# Eyebot_powerdist.net
KiCad netlist of a schematic drawn in EAGLE
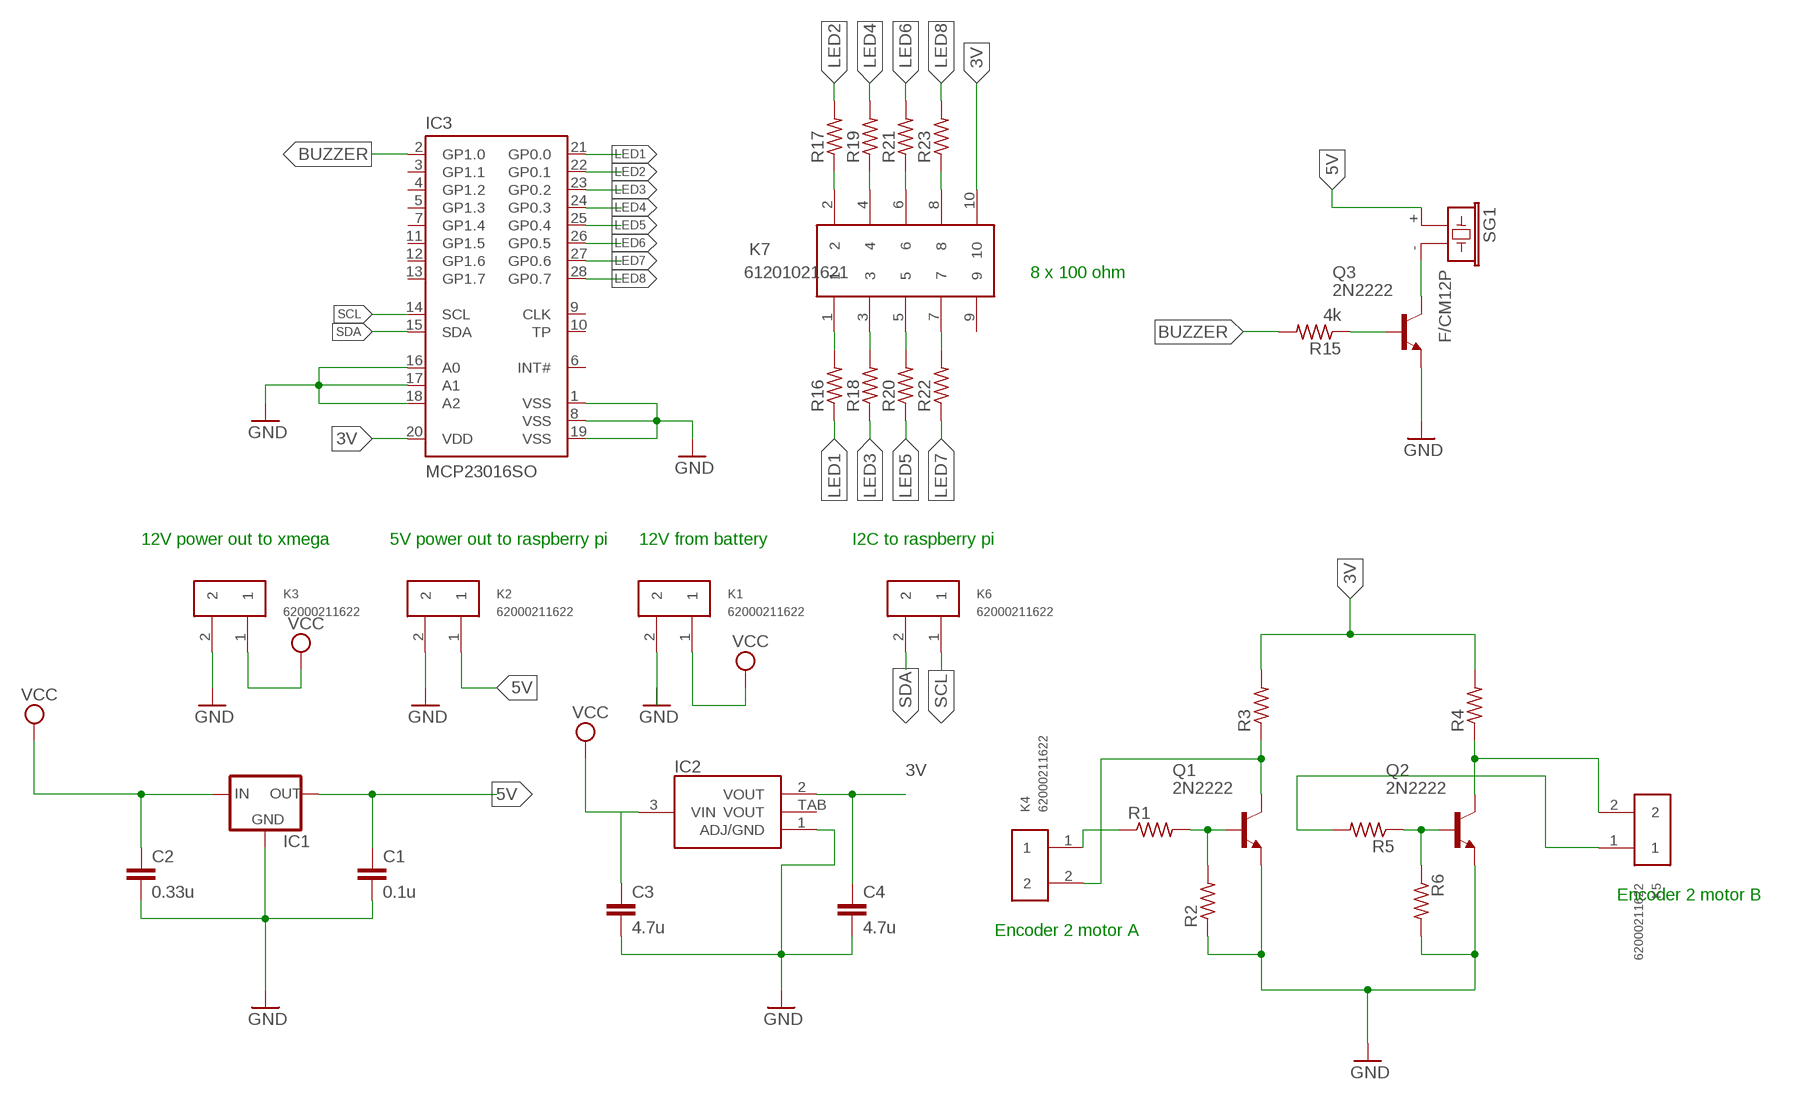
[diagram p0: schematic, sheet 1]

(export (version "E")
  (design (tool "Eeschema 10.0.6"))
  (components
    (comp (ref "C1")
      (value "0.1u")
      (footprint "eagle-import:AXIAL-5MM")
      (libsource (lib "eagle-import") (part "CAP_"))
    )
    (comp (ref "C2")
      (value "0.33u")
      (footprint "eagle-import:CAP-PTH-SMALL")
      (libsource (lib "eagle-import") (part "CAPPTH"))
    )
    (comp (ref "C3")
      (value "4.7u")
      (footprint "eagle-import:1206")
      (libsource (lib "eagle-import") (part "CAP1206"))
    )
    (comp (ref "C4")
      (value "4.7u")
      (footprint "eagle-import:1206")
      (libsource (lib "eagle-import") (part "CAP1206"))
    )
    (comp (ref "IC1")
      (value "V_REG_78XX-TO-220")
      (footprint "eagle-import:TO-220-ALT")
      (libsource (lib "eagle-import") (part "V_REG_78XX-TO-220"))
    )
    (comp (ref "IC2")
      (value "LDO1117-SOT223")
      (footprint "eagle-import:SOT223-3L")
      (libsource (lib "eagle-import") (part "LDO1117-SOT223"))
    )
    (comp (ref "IC3")
      (value "MCP23016SO")
      (footprint "eagle-import:SO-28W")
      (libsource (lib "eagle-import") (part "MCP23016SO"))
    )
    (comp (ref "K1")
      (value "62000211622")
      (footprint "eagle-import:62000211622")
      (libsource (lib "eagle-import") (part "62000211622"))
    )
    (comp (ref "K2")
      (value "62000211622")
      (footprint "eagle-import:62000211622")
      (libsource (lib "eagle-import") (part "62000211622"))
    )
    (comp (ref "K3")
      (value "62000211622")
      (footprint "eagle-import:62000211622")
      (libsource (lib "eagle-import") (part "62000211622"))
    )
    (comp (ref "K4")
      (value "62000211622")
      (footprint "eagle-import:62000211622")
      (libsource (lib "eagle-import") (part "62000211622"))
    )
    (comp (ref "K5")
      (value "62000211622")
      (footprint "eagle-import:62000211622")
      (libsource (lib "eagle-import") (part "62000211622"))
    )
    (comp (ref "K6")
      (value "62000211622")
      (footprint "eagle-import:62000211622")
      (libsource (lib "eagle-import") (part "62000211622"))
    )
    (comp (ref "K7")
      (value "61201021621")
      (footprint "eagle-import:61201021621")
      (libsource (lib "eagle-import") (part "61201021621"))
    )
    (comp (ref "Q1")
      (value "2N2222")
      (footprint "eagle-import:TO18")
      (libsource (lib "eagle-import") (part "2N2222"))
    )
    (comp (ref "Q2")
      (value "2N2222")
      (footprint "eagle-import:TO18")
      (libsource (lib "eagle-import") (part "2N2222"))
    )
    (comp (ref "Q3")
      (value "2N2222")
      (footprint "eagle-import:TO18")
      (libsource (lib "eagle-import") (part "2N2222"))
    )
    (comp (ref "R1")
      (value "R-US_0309/10")
      (footprint "eagle-import:0309_10")
      (libsource (lib "eagle-import") (part "R-US_0309/10"))
    )
    (comp (ref "R2")
      (value "R-US_0309/10")
      (footprint "eagle-import:0309_10")
      (libsource (lib "eagle-import") (part "R-US_0309/10"))
    )
    (comp (ref "R3")
      (value "R-US_0309/10")
      (footprint "eagle-import:0309_10")
      (libsource (lib "eagle-import") (part "R-US_0309/10"))
    )
    (comp (ref "R4")
      (value "R-US_0309/10")
      (footprint "eagle-import:0309_10")
      (libsource (lib "eagle-import") (part "R-US_0309/10"))
    )
    (comp (ref "R5")
      (value "R-US_0309/10")
      (footprint "eagle-import:0309_10")
      (libsource (lib "eagle-import") (part "R-US_0309/10"))
    )
    (comp (ref "R6")
      (value "R-US_0309/10")
      (footprint "eagle-import:0309_10")
      (libsource (lib "eagle-import") (part "R-US_0309/10"))
    )
    (comp (ref "R15")
      (value "4k")
      (footprint "eagle-import:0309_10")
      (libsource (lib "eagle-import") (part "R-US_0309/10"))
    )
    (comp (ref "R16")
      (value "R-US_0309/10")
      (footprint "eagle-import:0309_10")
      (libsource (lib "eagle-import") (part "R-US_0309/10"))
    )
    (comp (ref "R17")
      (value "R-US_0309/10")
      (footprint "eagle-import:0309_10")
      (libsource (lib "eagle-import") (part "R-US_0309/10"))
    )
    (comp (ref "R18")
      (value "R-US_0309/10")
      (footprint "eagle-import:0309_10")
      (libsource (lib "eagle-import") (part "R-US_0309/10"))
    )
    (comp (ref "R19")
      (value "R-US_0309/10")
      (footprint "eagle-import:0309_10")
      (libsource (lib "eagle-import") (part "R-US_0309/10"))
    )
    (comp (ref "R20")
      (value "R-US_0309/10")
      (footprint "eagle-import:0309_10")
      (libsource (lib "eagle-import") (part "R-US_0309/10"))
    )
    (comp (ref "R21")
      (value "R-US_0309/10")
      (footprint "eagle-import:0309_10")
      (libsource (lib "eagle-import") (part "R-US_0309/10"))
    )
    (comp (ref "R22")
      (value "R-US_0309/10")
      (footprint "eagle-import:0309_10")
      (libsource (lib "eagle-import") (part "R-US_0309/10"))
    )
    (comp (ref "R23")
      (value "R-US_0309/10")
      (footprint "eagle-import:0309_10")
      (libsource (lib "eagle-import") (part "R-US_0309/10"))
    )
    (comp (ref "SG1")
      (value "F/CM12P")
      (footprint "eagle-import:F_CM12P")
      (libsource (lib "eagle-import") (part "F/CM12P"))
    )
  )
  (nets
    (net (code "1") (name "3V") (class "Default")
      (node (ref "C4") (pin "1") (pinfunction "1_1") (pintype "passive"))
      (node (ref "IC2") (pin "2") (pinfunction "VOUT_2") (pintype "passive"))
      (node (ref "IC3") (pin "20") (pinfunction "VDD_20") (pintype "power_in"))
      (node (ref "K7") (pin "10") (pinfunction "10_10") (pintype "passive"))
      (node (ref "R3") (pin "2") (pinfunction "2_2") (pintype "passive"))
      (node (ref "R4") (pin "2") (pinfunction "2_2") (pintype "passive"))
    )
    (net (code "2") (name "5V") (class "Default")
      (node (ref "C1") (pin "P$1") (pinfunction "1_P$1") (pintype "passive"))
      (node (ref "IC1") (pin "OUT") (pinfunction "OUT_OUT") (pintype "output"))
      (node (ref "K2") (pin "1") (pinfunction "1_1") (pintype "bidirectional"))
      (node (ref "SG1") (pin "+") (pinfunction "1_+") (pintype "passive"))
    )
    (net (code "3") (name "BUZZER") (class "Default")
      (node (ref "IC3") (pin "2") (pinfunction "GP1.0_2") (pintype "bidirectional"))
      (node (ref "R15") (pin "2") (pinfunction "2_2") (pintype "passive"))
    )
    (net (code "4") (name "GND") (class "Default")
      (node (ref "C1") (pin "P$2") (pinfunction "2_P$2") (pintype "passive"))
      (node (ref "C2") (pin "2") (pinfunction "2_2") (pintype "passive"))
      (node (ref "C3") (pin "2") (pinfunction "2_2") (pintype "passive"))
      (node (ref "C4") (pin "2") (pinfunction "2_2") (pintype "passive"))
      (node (ref "IC1") (pin "GND") (pinfunction "GND_GND") (pintype "input"))
      (node (ref "IC2") (pin "1") (pinfunction "ADJ/GND_1") (pintype "passive"))
      (node (ref "IC3") (pin "1") (pinfunction "VSS_1") (pintype "power_in"))
      (node (ref "IC3") (pin "16") (pinfunction "A0_16") (pintype "input"))
      (node (ref "IC3") (pin "17") (pinfunction "A1_17") (pintype "input"))
      (node (ref "IC3") (pin "18") (pinfunction "A2_18") (pintype "input"))
      (node (ref "IC3") (pin "19") (pinfunction "VSS_19") (pintype "power_in"))
      (node (ref "IC3") (pin "8") (pinfunction "VSS_8") (pintype "power_in"))
      (node (ref "K1") (pin "2") (pinfunction "2_2") (pintype "bidirectional"))
      (node (ref "K2") (pin "2") (pinfunction "2_2") (pintype "bidirectional"))
      (node (ref "K3") (pin "2") (pinfunction "2_2") (pintype "bidirectional"))
      (node (ref "Q1") (pin "1") (pinfunction "E_1") (pintype "passive"))
      (node (ref "Q2") (pin "1") (pinfunction "E_1") (pintype "passive"))
      (node (ref "Q3") (pin "1") (pinfunction "E_1") (pintype "passive"))
      (node (ref "R2") (pin "1") (pinfunction "1_1") (pintype "passive"))
      (node (ref "R6") (pin "2") (pinfunction "2_2") (pintype "passive"))
    )
    (net (code "5") (name "LED1") (class "Default")
      (node (ref "IC3") (pin "21") (pinfunction "GP0.0_21") (pintype "bidirectional"))
      (node (ref "R16") (pin "1") (pinfunction "1_1") (pintype "passive"))
    )
    (net (code "6") (name "LED2") (class "Default")
      (node (ref "IC3") (pin "22") (pinfunction "GP0.1_22") (pintype "bidirectional"))
      (node (ref "R17") (pin "2") (pinfunction "2_2") (pintype "passive"))
    )
    (net (code "7") (name "LED3") (class "Default")
      (node (ref "IC3") (pin "23") (pinfunction "GP0.2_23") (pintype "bidirectional"))
      (node (ref "R18") (pin "1") (pinfunction "1_1") (pintype "passive"))
    )
    (net (code "8") (name "LED4") (class "Default")
      (node (ref "IC3") (pin "24") (pinfunction "GP0.3_24") (pintype "bidirectional"))
      (node (ref "R19") (pin "2") (pinfunction "2_2") (pintype "passive"))
    )
    (net (code "9") (name "LED5") (class "Default")
      (node (ref "IC3") (pin "25") (pinfunction "GP0.4_25") (pintype "bidirectional"))
      (node (ref "R20") (pin "1") (pinfunction "1_1") (pintype "passive"))
    )
    (net (code "10") (name "LED6") (class "Default")
      (node (ref "IC3") (pin "26") (pinfunction "GP0.5_26") (pintype "bidirectional"))
      (node (ref "R21") (pin "2") (pinfunction "2_2") (pintype "passive"))
    )
    (net (code "11") (name "LED7") (class "Default")
      (node (ref "IC3") (pin "27") (pinfunction "GP0.6_27") (pintype "bidirectional"))
      (node (ref "R22") (pin "1") (pinfunction "1_1") (pintype "passive"))
    )
    (net (code "12") (name "LED8") (class "Default")
      (node (ref "IC3") (pin "28") (pinfunction "GP0.7_28") (pintype "bidirectional"))
      (node (ref "R23") (pin "2") (pinfunction "2_2") (pintype "passive"))
    )
    (net (code "13") (name "Net-(K4-Pad1)") (class "Default")
      (node (ref "K4") (pin "1") (pinfunction "1_1") (pintype "bidirectional"))
      (node (ref "R1") (pin "1") (pinfunction "1_1") (pintype "passive"))
    )
    (net (code "14") (name "Net-(K5-Pad1)") (class "Default")
      (node (ref "K5") (pin "1") (pinfunction "1_1") (pintype "bidirectional"))
      (node (ref "R5") (pin "2") (pinfunction "2_2") (pintype "passive"))
    )
    (net (code "15") (name "Net-(K7-Pad1)") (class "Default")
      (node (ref "K7") (pin "1") (pinfunction "1_1") (pintype "passive"))
      (node (ref "R16") (pin "2") (pinfunction "2_2") (pintype "passive"))
    )
    (net (code "16") (name "Net-(K7-Pad2)") (class "Default")
      (node (ref "K7") (pin "2") (pinfunction "2_2") (pintype "passive"))
      (node (ref "R17") (pin "1") (pinfunction "1_1") (pintype "passive"))
    )
    (net (code "17") (name "Net-(K7-Pad3)") (class "Default")
      (node (ref "K7") (pin "3") (pinfunction "3_3") (pintype "passive"))
      (node (ref "R18") (pin "2") (pinfunction "2_2") (pintype "passive"))
    )
    (net (code "18") (name "Net-(K7-Pad4)") (class "Default")
      (node (ref "K7") (pin "4") (pinfunction "4_4") (pintype "passive"))
      (node (ref "R19") (pin "1") (pinfunction "1_1") (pintype "passive"))
    )
    (net (code "19") (name "Net-(K7-Pad5)") (class "Default")
      (node (ref "K7") (pin "5") (pinfunction "5_5") (pintype "passive"))
      (node (ref "R20") (pin "2") (pinfunction "2_2") (pintype "passive"))
    )
    (net (code "20") (name "Net-(K7-Pad6)") (class "Default")
      (node (ref "K7") (pin "6") (pinfunction "6_6") (pintype "passive"))
      (node (ref "R21") (pin "1") (pinfunction "1_1") (pintype "passive"))
    )
    (net (code "21") (name "Net-(K7-Pad7)") (class "Default")
      (node (ref "K7") (pin "7") (pinfunction "7_7") (pintype "passive"))
      (node (ref "R22") (pin "2") (pinfunction "2_2") (pintype "passive"))
    )
    (net (code "22") (name "Net-(K7-Pad8)") (class "Default")
      (node (ref "K7") (pin "8") (pinfunction "8_8") (pintype "passive"))
      (node (ref "R23") (pin "1") (pinfunction "1_1") (pintype "passive"))
    )
    (net (code "23") (name "Net-(Q1-B)") (class "Default")
      (node (ref "Q1") (pin "2") (pinfunction "B_2") (pintype "passive"))
      (node (ref "R1") (pin "2") (pinfunction "2_2") (pintype "passive"))
      (node (ref "R2") (pin "2") (pinfunction "2_2") (pintype "passive"))
    )
    (net (code "24") (name "Net-(Q1-C)") (class "Default")
      (node (ref "K4") (pin "2") (pinfunction "2_2") (pintype "bidirectional"))
      (node (ref "Q1") (pin "3") (pinfunction "C_3") (pintype "passive"))
      (node (ref "R3") (pin "1") (pinfunction "1_1") (pintype "passive"))
    )
    (net (code "25") (name "Net-(Q2-B)") (class "Default")
      (node (ref "Q2") (pin "2") (pinfunction "B_2") (pintype "passive"))
      (node (ref "R5") (pin "1") (pinfunction "1_1") (pintype "passive"))
      (node (ref "R6") (pin "1") (pinfunction "1_1") (pintype "passive"))
    )
    (net (code "26") (name "Net-(Q2-C)") (class "Default")
      (node (ref "K5") (pin "2") (pinfunction "2_2") (pintype "bidirectional"))
      (node (ref "Q2") (pin "3") (pinfunction "C_3") (pintype "passive"))
      (node (ref "R4") (pin "1") (pinfunction "1_1") (pintype "passive"))
    )
    (net (code "27") (name "Net-(Q3-B)") (class "Default")
      (node (ref "Q3") (pin "2") (pinfunction "B_2") (pintype "passive"))
      (node (ref "R15") (pin "1") (pinfunction "1_1") (pintype "passive"))
    )
    (net (code "28") (name "Net-(Q3-C)") (class "Default")
      (node (ref "Q3") (pin "3") (pinfunction "C_3") (pintype "passive"))
      (node (ref "SG1") (pin "-") (pinfunction "2_-") (pintype "passive"))
    )
    (net (code "29") (name "SCL") (class "Default")
      (node (ref "IC3") (pin "14") (pinfunction "SCL_14") (pintype "input"))
      (node (ref "K6") (pin "1") (pinfunction "1_1") (pintype "bidirectional"))
    )
    (net (code "30") (name "SDA") (class "Default")
      (node (ref "IC3") (pin "15") (pinfunction "SDA_15") (pintype "bidirectional"))
      (node (ref "K6") (pin "2") (pinfunction "2_2") (pintype "bidirectional"))
    )
    (net (code "31") (name "VCC") (class "Default")
      (node (ref "C2") (pin "1") (pinfunction "1_1") (pintype "passive"))
      (node (ref "C3") (pin "1") (pinfunction "1_1") (pintype "passive"))
      (node (ref "IC1") (pin "IN") (pinfunction "IN_IN") (pintype "input"))
      (node (ref "IC2") (pin "3") (pinfunction "VIN_3") (pintype "passive"))
      (node (ref "K1") (pin "1") (pinfunction "1_1") (pintype "bidirectional"))
      (node (ref "K3") (pin "1") (pinfunction "1_1") (pintype "bidirectional"))
    )
    (net (code "32") (name "unconnected-(IC2-VOUT-PadTAB)") (class "Default")
      (node (ref "IC2") (pin "TAB") (pinfunction "VOUT_TAB") (pintype "passive"))
    )
    (net (code "33") (name "unconnected-(IC3-CLK-Pad9)") (class "Default")
      (node (ref "IC3") (pin "9") (pinfunction "CLK_9") (pintype "input"))
    )
    (net (code "34") (name "unconnected-(IC3-GP1.1-Pad3)") (class "Default")
      (node (ref "IC3") (pin "3") (pinfunction "GP1.1_3") (pintype "bidirectional"))
    )
    (net (code "35") (name "unconnected-(IC3-GP1.2-Pad4)") (class "Default")
      (node (ref "IC3") (pin "4") (pinfunction "GP1.2_4") (pintype "bidirectional"))
    )
    (net (code "36") (name "unconnected-(IC3-GP1.3-Pad5)") (class "Default")
      (node (ref "IC3") (pin "5") (pinfunction "GP1.3_5") (pintype "bidirectional"))
    )
    (net (code "37") (name "unconnected-(IC3-GP1.4-Pad7)") (class "Default")
      (node (ref "IC3") (pin "7") (pinfunction "GP1.4_7") (pintype "bidirectional"))
    )
    (net (code "38") (name "unconnected-(IC3-GP1.5-Pad11)") (class "Default")
      (node (ref "IC3") (pin "11") (pinfunction "GP1.5_11") (pintype "bidirectional"))
    )
    (net (code "39") (name "unconnected-(IC3-GP1.6-Pad12)") (class "Default")
      (node (ref "IC3") (pin "12") (pinfunction "GP1.6_12") (pintype "bidirectional"))
    )
    (net (code "40") (name "unconnected-(IC3-GP1.7-Pad13)") (class "Default")
      (node (ref "IC3") (pin "13") (pinfunction "GP1.7_13") (pintype "bidirectional"))
    )
    (net (code "41") (name "unconnected-(IC3-INT#-Pad6)") (class "Default")
      (node (ref "IC3") (pin "6") (pinfunction "INT#_6") (pintype "output"))
    )
    (net (code "42") (name "unconnected-(IC3-TP-Pad10)") (class "Default")
      (node (ref "IC3") (pin "10") (pinfunction "TP_10") (pintype "output"))
    )
    (net (code "43") (name "unconnected-(K7-Pad9)") (class "Default")
      (node (ref "K7") (pin "9") (pinfunction "9_9") (pintype "passive"))
    )
  )
)
